# Schematic.net
KiCad netlist of a schematic drawn in EAGLE
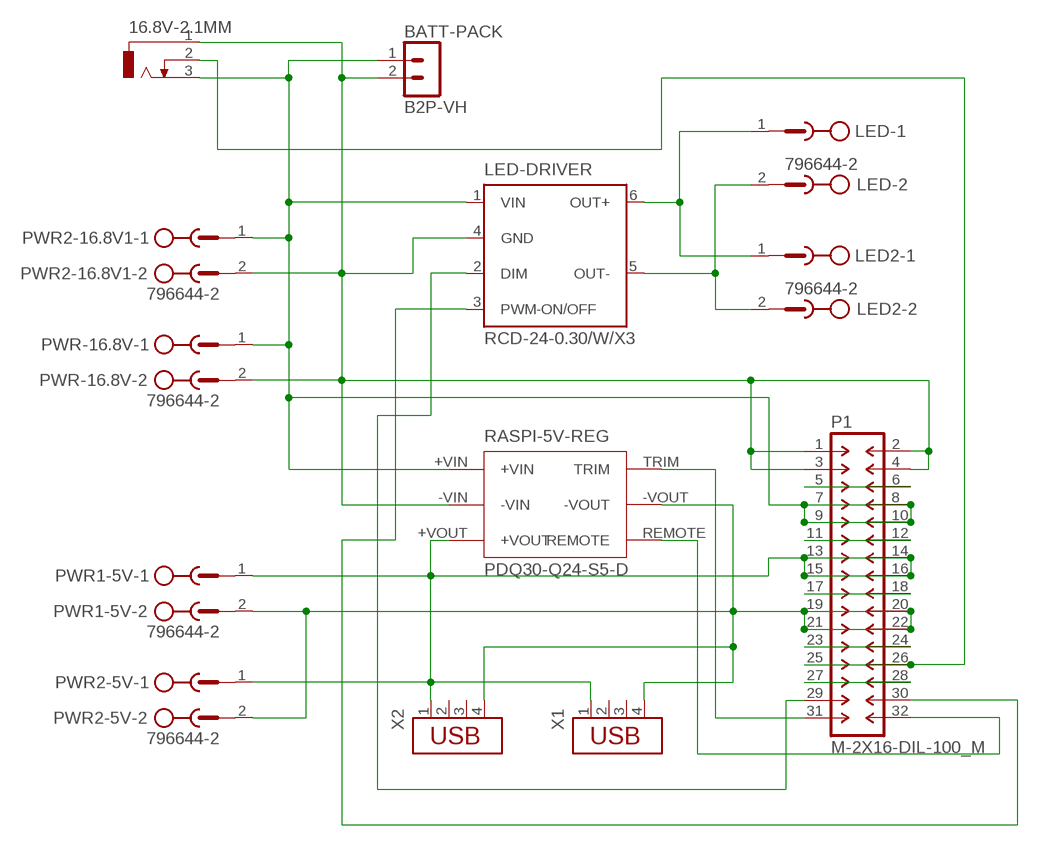
[diagram p0: schematic, sheet 1]

(export (version "E")
  (design (tool "Eeschema 10.0.6"))
  (components
    (comp (ref "16.8V-2.1MM")
      (value "DCJ0303")
      (footprint "eagle-import:DCJ0303")
      (libsource (lib "eagle-import") (part "DCJ0303"))
    )
    (comp (ref "BATT-PACK")
      (value "B2P-VH")
      (footprint "eagle-import:B2P-VH")
      (libsource (lib "eagle-import") (part "B2P-VH"))
    )
    (comp (ref "LED")
      (value "796644-2")
      (footprint "eagle-import:796644-2")
      (libsource (lib "eagle-import") (part "796644-2"))
    )
    (comp (ref "LED-DRIVER")
      (value "RCD-24-0.30/W/X3")
      (footprint "eagle-import:RCD-24_W_X3")
      (libsource (lib "eagle-import") (part "RCD-24/W/X3-0.30"))
    )
    (comp (ref "LED2")
      (value "796644-2")
      (footprint "eagle-import:796644-2")
      (libsource (lib "eagle-import") (part "796644-2"))
    )
    (comp (ref "P1")
      (value "M-2X16-DIL-100_M")
      (footprint "eagle-import:DIL-100-2X16_M")
      (libsource (lib "eagle-import") (part "M-2X16-DIL-100_M"))
    )
    (comp (ref "PWR-16.8V")
      (value "796644-2")
      (footprint "eagle-import:796644-2")
      (libsource (lib "eagle-import") (part "796644-2"))
    )
    (comp (ref "PWR1-5V")
      (value "796644-2")
      (footprint "eagle-import:796644-2")
      (libsource (lib "eagle-import") (part "796644-2"))
    )
    (comp (ref "PWR2-5V")
      (value "796644-2")
      (footprint "eagle-import:796644-2")
      (libsource (lib "eagle-import") (part "796644-2"))
    )
    (comp (ref "PWR2-16.8V1")
      (value "796644-2")
      (footprint "eagle-import:796644-2")
      (libsource (lib "eagle-import") (part "796644-2"))
    )
    (comp (ref "RASPI-5V-REG")
      (value "PDQ30-Q24-S5-D")
      (footprint "eagle-import:PDQ30-Q24-S5-D")
      (libsource (lib "eagle-import") (part "PDQ30-Q24-S5-D"))
    )
    (comp (ref "X1")
      (value "USB-787616")
      (footprint "eagle-import:USB")
      (libsource (lib "eagle-import") (part "USB-787616"))
    )
    (comp (ref "X2")
      (value "USB-787616")
      (footprint "eagle-import:USB")
      (libsource (lib "eagle-import") (part "USB-787616"))
    )
  )
  (nets
    (net (code "1") (name "Net-(16.8V-2.1MM-Pad2)") (class "Default")
      (node (ref "16.8V-2.1MM") (pin "2") (pinfunction "2_2") (pintype "passive"))
      (node (ref "P1") (pin "25") (pinfunction "25_25") (pintype "passive"))
      (node (ref "P1") (pin "26") (pinfunction "26_26") (pintype "passive"))
    )
    (net (code "2") (name "Net-(LED-DRIVER-DIM)") (class "Default")
      (node (ref "LED-DRIVER") (pin "2") (pinfunction "DIM_2") (pintype "passive"))
      (node (ref "P1") (pin "29") (pinfunction "29_29") (pintype "passive"))
    )
    (net (code "3") (name "Net-(LED-DRIVER-GND)") (class "Default")
      (node (ref "16.8V-2.1MM") (pin "1") (pinfunction "1_1") (pintype "passive"))
      (node (ref "BATT-PACK") (pin "2") (pinfunction "2_2") (pintype "passive"))
      (node (ref "LED-DRIVER") (pin "4") (pinfunction "GND_4") (pintype "power_in"))
      (node (ref "P1") (pin "1") (pinfunction "1_1") (pintype "passive"))
      (node (ref "P1") (pin "2") (pinfunction "2_2") (pintype "passive"))
      (node (ref "P1") (pin "3") (pinfunction "3_3") (pintype "passive"))
      (node (ref "P1") (pin "4") (pinfunction "4_4") (pintype "passive"))
      (node (ref "PWR-16.8V") (pin "2") (pinfunction "SK_2") (pintype "passive"))
      (node (ref "PWR2-16.8V1") (pin "2") (pinfunction "SK_2") (pintype "passive"))
      (node (ref "RASPI-5V-REG") (pin "-VIN") (pinfunction "-VIN_-VIN") (pintype "bidirectional"))
    )
    (net (code "4") (name "Net-(LED-DRIVER-OUT+)") (class "Default")
      (node (ref "LED") (pin "1") (pinfunction "SK_1") (pintype "passive"))
      (node (ref "LED-DRIVER") (pin "6") (pinfunction "OUT+_6") (pintype "output"))
      (node (ref "LED2") (pin "1") (pinfunction "SK_1") (pintype "passive"))
    )
    (net (code "5") (name "Net-(LED-DRIVER-OUT-)") (class "Default")
      (node (ref "LED") (pin "2") (pinfunction "SK_2") (pintype "passive"))
      (node (ref "LED-DRIVER") (pin "5") (pinfunction "OUT-_5") (pintype "output"))
      (node (ref "LED2") (pin "2") (pinfunction "SK_2") (pintype "passive"))
    )
    (net (code "6") (name "Net-(LED-DRIVER-PWM-ON{slash}OFF)") (class "Default")
      (node (ref "LED-DRIVER") (pin "3") (pinfunction "PWM-ON/OFF_3") (pintype "passive"))
      (node (ref "P1") (pin "30") (pinfunction "30_30") (pintype "passive"))
    )
    (net (code "7") (name "Net-(LED-DRIVER-VIN)") (class "Default")
      (node (ref "16.8V-2.1MM") (pin "3") (pinfunction "3_3") (pintype "passive"))
      (node (ref "BATT-PACK") (pin "1") (pinfunction "1_1") (pintype "passive"))
      (node (ref "LED-DRIVER") (pin "1") (pinfunction "VIN_1") (pintype "input"))
      (node (ref "P1") (pin "10") (pinfunction "10_10") (pintype "passive"))
      (node (ref "P1") (pin "7") (pinfunction "7_7") (pintype "passive"))
      (node (ref "P1") (pin "8") (pinfunction "8_8") (pintype "passive"))
      (node (ref "P1") (pin "9") (pinfunction "9_9") (pintype "passive"))
      (node (ref "PWR-16.8V") (pin "1") (pinfunction "SK_1") (pintype "passive"))
      (node (ref "PWR2-16.8V1") (pin "1") (pinfunction "SK_1") (pintype "passive"))
      (node (ref "RASPI-5V-REG") (pin "+VIN") (pinfunction "+VIN_+VIN") (pintype "bidirectional"))
    )
    (net (code "8") (name "Net-(P1-Pad5)") (class "Default")
      (node (ref "P1") (pin "5") (pinfunction "5_5") (pintype "passive"))
      (node (ref "P1") (pin "6") (pinfunction "6_6") (pintype "passive"))
    )
    (net (code "9") (name "Net-(P1-Pad11)") (class "Default")
      (node (ref "P1") (pin "11") (pinfunction "11_11") (pintype "passive"))
      (node (ref "P1") (pin "12") (pinfunction "12_12") (pintype "passive"))
    )
    (net (code "10") (name "Net-(P1-Pad17)") (class "Default")
      (node (ref "P1") (pin "17") (pinfunction "17_17") (pintype "passive"))
      (node (ref "P1") (pin "18") (pinfunction "18_18") (pintype "passive"))
    )
    (net (code "11") (name "Net-(P1-Pad23)") (class "Default")
      (node (ref "P1") (pin "23") (pinfunction "23_23") (pintype "passive"))
      (node (ref "P1") (pin "24") (pinfunction "24_24") (pintype "passive"))
    )
    (net (code "12") (name "Net-(P1-Pad27)") (class "Default")
      (node (ref "P1") (pin "27") (pinfunction "27_27") (pintype "passive"))
      (node (ref "P1") (pin "28") (pinfunction "28_28") (pintype "passive"))
    )
    (net (code "13") (name "Net-(P1-Pad31)") (class "Default")
      (node (ref "P1") (pin "31") (pinfunction "31_31") (pintype "passive"))
      (node (ref "RASPI-5V-REG") (pin "TRIM") (pinfunction "TRIM_TRIM") (pintype "bidirectional"))
    )
    (net (code "14") (name "Net-(P1-Pad32)") (class "Default")
      (node (ref "P1") (pin "32") (pinfunction "32_32") (pintype "passive"))
      (node (ref "RASPI-5V-REG") (pin "REMOTE") (pinfunction "REMOTE_REMOTE") (pintype "bidirectional"))
    )
    (net (code "15") (name "Net-(PWR1-5VA-SK)") (class "Default")
      (node (ref "P1") (pin "13") (pinfunction "13_13") (pintype "passive"))
      (node (ref "P1") (pin "14") (pinfunction "14_14") (pintype "passive"))
      (node (ref "P1") (pin "15") (pinfunction "15_15") (pintype "passive"))
      (node (ref "P1") (pin "16") (pinfunction "16_16") (pintype "passive"))
      (node (ref "PWR1-5V") (pin "1") (pinfunction "SK_1") (pintype "passive"))
      (node (ref "PWR2-5V") (pin "1") (pinfunction "SK_1") (pintype "passive"))
      (node (ref "RASPI-5V-REG") (pin "+VOUT") (pinfunction "+VOUT_+VOUT") (pintype "bidirectional"))
      (node (ref "X1") (pin "1") (pinfunction "1_1") (pintype "passive"))
      (node (ref "X2") (pin "1") (pinfunction "1_1") (pintype "passive"))
    )
    (net (code "16") (name "Net-(PWR1-5VB-SK)") (class "Default")
      (node (ref "P1") (pin "19") (pinfunction "19_19") (pintype "passive"))
      (node (ref "P1") (pin "20") (pinfunction "20_20") (pintype "passive"))
      (node (ref "P1") (pin "21") (pinfunction "21_21") (pintype "passive"))
      (node (ref "P1") (pin "22") (pinfunction "22_22") (pintype "passive"))
      (node (ref "PWR1-5V") (pin "2") (pinfunction "SK_2") (pintype "passive"))
      (node (ref "PWR2-5V") (pin "2") (pinfunction "SK_2") (pintype "passive"))
      (node (ref "RASPI-5V-REG") (pin "-VOUT") (pinfunction "-VOUT_-VOUT") (pintype "bidirectional"))
      (node (ref "X1") (pin "4") (pinfunction "4_4") (pintype "passive"))
      (node (ref "X2") (pin "4") (pinfunction "4_4") (pintype "passive"))
    )
    (net (code "17") (name "unconnected-(X1-Pad2)") (class "Default")
      (node (ref "X1") (pin "2") (pinfunction "2_2") (pintype "passive"))
    )
    (net (code "18") (name "unconnected-(X1-Pad3)") (class "Default")
      (node (ref "X1") (pin "3") (pinfunction "3_3") (pintype "passive"))
    )
    (net (code "19") (name "unconnected-(X2-Pad2)") (class "Default")
      (node (ref "X2") (pin "2") (pinfunction "2_2") (pintype "passive"))
    )
    (net (code "20") (name "unconnected-(X2-Pad3)") (class "Default")
      (node (ref "X2") (pin "3") (pinfunction "3_3") (pintype "passive"))
    )
  )
)
